# pycopter_board_v1.net
KiCad netlist of a schematic drawn in EAGLE
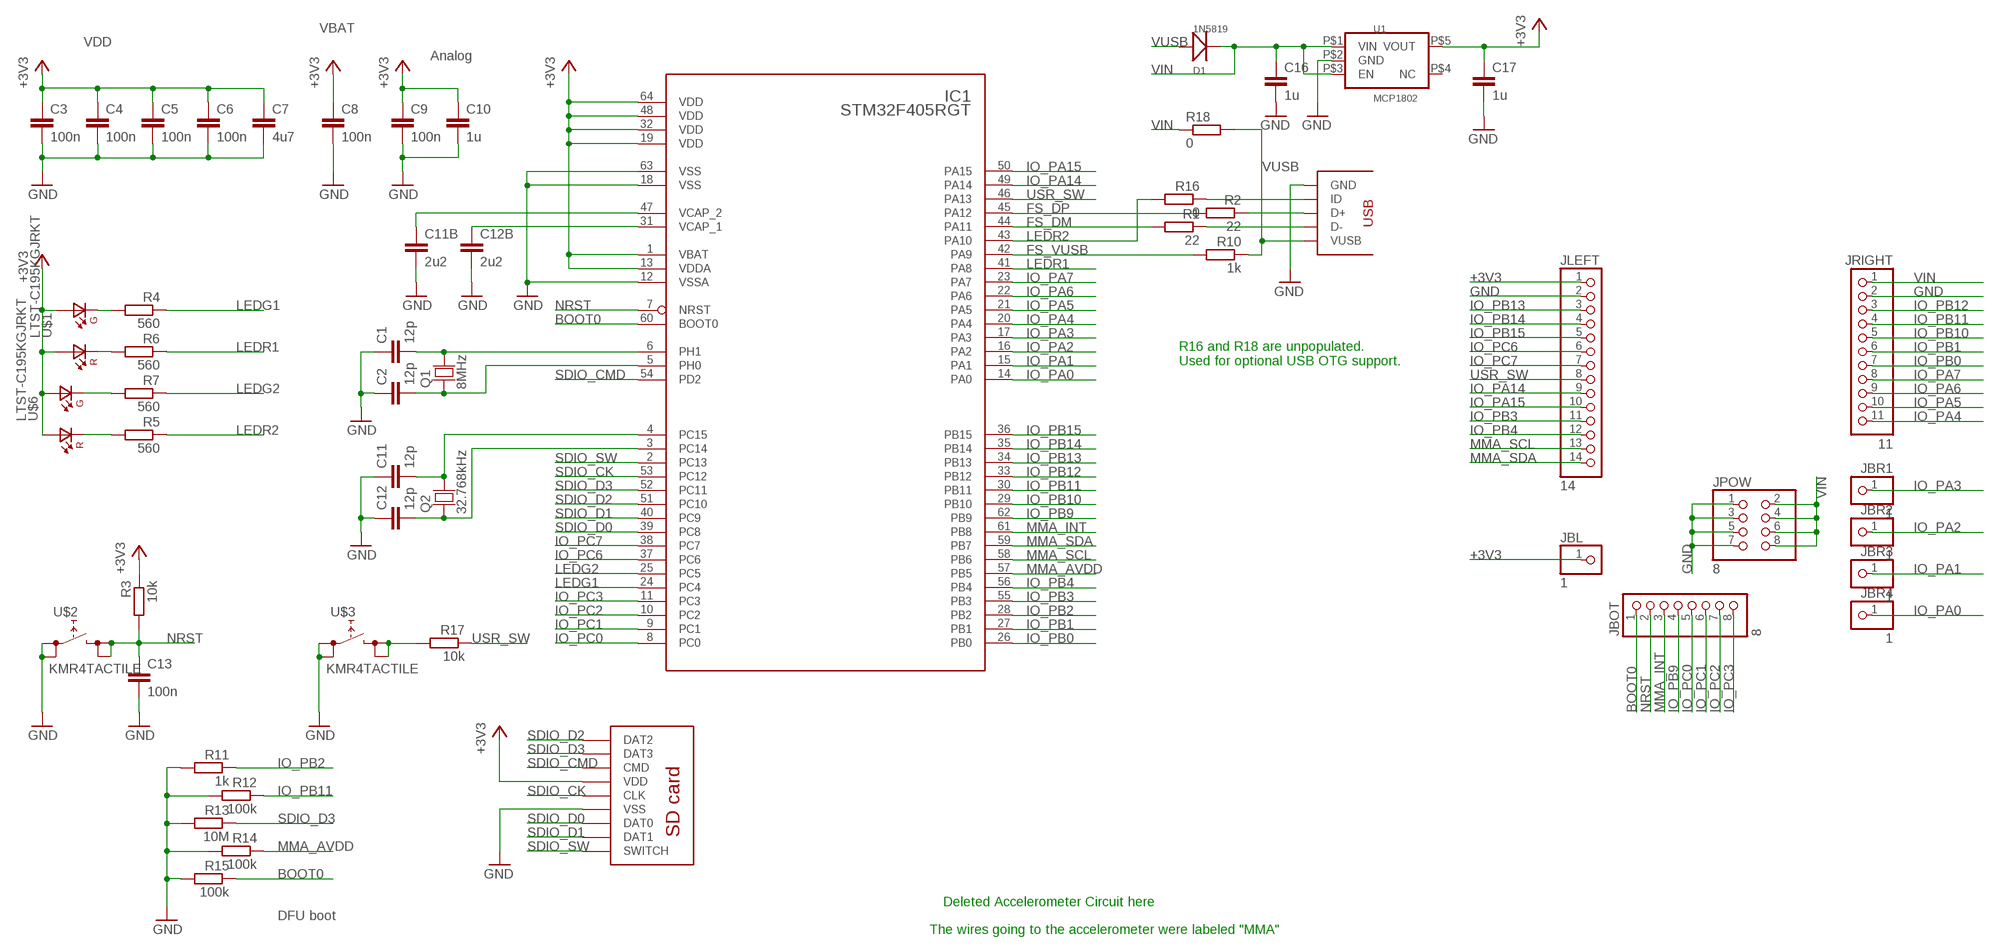
[diagram p0: schematic, sheet 1]

(export (version "E")
  (design (tool "Eeschema 10.0.6"))
  (components
    (comp (ref "C1")
      (value "12p")
      (footprint "eagle-import:C0603")
      (libsource (lib "eagle-import") (part "C-EUC0603"))
    )
    (comp (ref "C2")
      (value "12p")
      (footprint "eagle-import:C0603")
      (libsource (lib "eagle-import") (part "C-EUC0603"))
    )
    (comp (ref "C3")
      (value "100n")
      (footprint "eagle-import:C0603")
      (libsource (lib "eagle-import") (part "C-EUC0603"))
    )
    (comp (ref "C4")
      (value "100n")
      (footprint "eagle-import:C0603")
      (libsource (lib "eagle-import") (part "C-EUC0603"))
    )
    (comp (ref "C5")
      (value "100n")
      (footprint "eagle-import:C0603")
      (libsource (lib "eagle-import") (part "C-EUC0603"))
    )
    (comp (ref "C6")
      (value "100n")
      (footprint "eagle-import:C0603")
      (libsource (lib "eagle-import") (part "C-EUC0603"))
    )
    (comp (ref "C7")
      (value "4u7")
      (footprint "eagle-import:C0603")
      (libsource (lib "eagle-import") (part "C-EUC0603"))
    )
    (comp (ref "C8")
      (value "100n")
      (footprint "eagle-import:C0603")
      (libsource (lib "eagle-import") (part "C-EUC0603"))
    )
    (comp (ref "C9")
      (value "100n")
      (footprint "eagle-import:C0603")
      (libsource (lib "eagle-import") (part "C-EUC0603"))
    )
    (comp (ref "C10")
      (value "1u")
      (footprint "eagle-import:C0603")
      (libsource (lib "eagle-import") (part "C-EUC0603"))
    )
    (comp (ref "C11")
      (value "12p")
      (footprint "eagle-import:C0603")
      (libsource (lib "eagle-import") (part "C-EUC0603"))
    )
    (comp (ref "C11B")
      (value "2u2")
      (footprint "eagle-import:C0603")
      (libsource (lib "eagle-import") (part "C-EUC0603"))
    )
    (comp (ref "C12")
      (value "12p")
      (footprint "eagle-import:C0603")
      (libsource (lib "eagle-import") (part "C-EUC0603"))
    )
    (comp (ref "C12B")
      (value "2u2")
      (footprint "eagle-import:C0603")
      (libsource (lib "eagle-import") (part "C-EUC0603"))
    )
    (comp (ref "C13")
      (value "100n")
      (footprint "eagle-import:C0603")
      (libsource (lib "eagle-import") (part "C-EUC0603"))
    )
    (comp (ref "C16")
      (value "1u")
      (footprint "eagle-import:C0603")
      (libsource (lib "eagle-import") (part "C-EUC0603"))
    )
    (comp (ref "C17")
      (value "1u")
      (footprint "eagle-import:C0603")
      (libsource (lib "eagle-import") (part "C-EUC0603"))
    )
    (comp (ref "D1")
      (value "1N5819")
      (footprint "eagle-import:SOD-123")
      (libsource (lib "eagle-import") (part "1N5819"))
    )
    (comp (ref "IC1")
      (value "STM32F405RGT")
      (footprint "eagle-import:LQFP64")
      (libsource (lib "eagle-import") (part "STM32F405RTG"))
    )
    (comp (ref "JBL")
      (value "1")
      (footprint "eagle-import:1X01")
      (libsource (lib "eagle-import") (part "PINHD-1X1"))
    )
    (comp (ref "JBOT")
      (value "8")
      (footprint "eagle-import:1X08")
      (libsource (lib "eagle-import") (part "PINHD-1X8"))
    )
    (comp (ref "JBR1")
      (value "1")
      (footprint "eagle-import:1X01")
      (libsource (lib "eagle-import") (part "PINHD-1X1"))
    )
    (comp (ref "JBR2")
      (value "1")
      (footprint "eagle-import:1X01")
      (libsource (lib "eagle-import") (part "PINHD-1X1"))
    )
    (comp (ref "JBR3")
      (value "1")
      (footprint "eagle-import:1X01")
      (libsource (lib "eagle-import") (part "PINHD-1X1"))
    )
    (comp (ref "JBR4")
      (value "1")
      (footprint "eagle-import:1X01")
      (libsource (lib "eagle-import") (part "PINHD-1X1"))
    )
    (comp (ref "JLEFT")
      (value "14")
      (footprint "eagle-import:1X14")
      (libsource (lib "eagle-import") (part "PINHD-1X14"))
    )
    (comp (ref "JPOW")
      (value "8")
      (footprint "eagle-import:2X04")
      (libsource (lib "eagle-import") (part "PINHD-2X4"))
    )
    (comp (ref "JRIGHT")
      (value "11")
      (footprint "eagle-import:1X11")
      (libsource (lib "eagle-import") (part "PINHD-1X11"))
    )
    (comp (ref "Q1")
      (value "8MHz")
      (footprint "eagle-import:TXC-SMD-50X32")
      (libsource (lib "eagle-import") (part "TXC-CRYSTAL50X32"))
    )
    (comp (ref "Q2")
      (value "32.768kHz")
      (footprint "eagle-import:TXC-SMD-32X15")
      (libsource (lib "eagle-import") (part "TXC-CRYSTAL32X15"))
    )
    (comp (ref "R1")
      (value "22")
      (footprint "eagle-import:R0603")
      (libsource (lib "eagle-import") (part "R-EU_R0603"))
    )
    (comp (ref "R2")
      (value "22")
      (footprint "eagle-import:R0603")
      (libsource (lib "eagle-import") (part "R-EU_R0603"))
    )
    (comp (ref "R3")
      (value "10k")
      (footprint "eagle-import:R0603")
      (libsource (lib "eagle-import") (part "R-EU_R0603"))
    )
    (comp (ref "R4")
      (value "560")
      (footprint "eagle-import:R0603")
      (libsource (lib "eagle-import") (part "R-EU_R0603"))
    )
    (comp (ref "R5")
      (value "560")
      (footprint "eagle-import:R0603")
      (libsource (lib "eagle-import") (part "R-EU_R0603"))
    )
    (comp (ref "R6")
      (value "560")
      (footprint "eagle-import:R0603")
      (libsource (lib "eagle-import") (part "R-EU_R0603"))
    )
    (comp (ref "R7")
      (value "560")
      (footprint "eagle-import:R0603")
      (libsource (lib "eagle-import") (part "R-EU_R0603"))
    )
    (comp (ref "R10")
      (value "1k")
      (footprint "eagle-import:R0603")
      (libsource (lib "eagle-import") (part "R-EU_R0603"))
    )
    (comp (ref "R11")
      (value "1k")
      (footprint "eagle-import:R0603")
      (libsource (lib "eagle-import") (part "R-EU_R0603"))
    )
    (comp (ref "R12")
      (value "100k")
      (footprint "eagle-import:R0603")
      (libsource (lib "eagle-import") (part "R-EU_R0603"))
    )
    (comp (ref "R13")
      (value "10M")
      (footprint "eagle-import:R0603")
      (libsource (lib "eagle-import") (part "R-EU_R0603"))
    )
    (comp (ref "R14")
      (value "100k")
      (footprint "eagle-import:R0603")
      (libsource (lib "eagle-import") (part "R-EU_R0603"))
    )
    (comp (ref "R15")
      (value "100k")
      (footprint "eagle-import:R0603")
      (libsource (lib "eagle-import") (part "R-EU_R0603"))
    )
    (comp (ref "R16")
      (value "0")
      (footprint "eagle-import:R0603")
      (libsource (lib "eagle-import") (part "R-EU_R0603"))
    )
    (comp (ref "R17")
      (value "10k")
      (footprint "eagle-import:R0603")
      (libsource (lib "eagle-import") (part "R-EU_R0603"))
    )
    (comp (ref "R18")
      (value "0")
      (footprint "eagle-import:R0805")
      (libsource (lib "eagle-import") (part "R-EU_R0805"))
    )
    (comp (ref "U$1")
      (value "LTST-C195KGJRKT")
      (footprint "eagle-import:LTST-BILED-15X16")
      (libsource (lib "eagle-import") (part "LTST-C195KGJRKT"))
    )
    (comp (ref "U$2")
      (value "KMR4TACTILE")
      (footprint "eagle-import:KMR4SWITCH")
      (libsource (lib "eagle-import") (part "KMR4TACTILE"))
    )
    (comp (ref "U$3")
      (value "KMR4TACTILE")
      (footprint "eagle-import:KMR4SWITCH")
      (libsource (lib "eagle-import") (part "KMR4TACTILE"))
    )
    (comp (ref "U$4")
      (value "MOLEX-SD-105027")
      (footprint "eagle-import:MOLEX-SD-105027-PKG")
      (libsource (lib "eagle-import") (part "MOLEX-SD-105027"))
    )
    (comp (ref "U$6")
      (value "LTST-C195KGJRKT")
      (footprint "eagle-import:LTST-BILED-15X16")
      (libsource (lib "eagle-import") (part "LTST-C195KGJRKT"))
    )
    (comp (ref "U$7")
      (value "USB-MICRO-AB")
      (footprint "eagle-import:HRS-USB-ZX62D-AB-5P8-PKG")
      (libsource (lib "eagle-import") (part "USB-MICRO-AB"))
    )
    (comp (ref "U1")
      (value "MCP1802")
      (footprint "eagle-import:SOT-23-5")
      (libsource (lib "eagle-import") (part "MCP1802"))
    )
  )
  (nets
    (net (code "1") (name "+3V3") (class "Default")
      (node (ref "C10") (pin "1") (pinfunction "1_1") (pintype "passive"))
      (node (ref "C17") (pin "1") (pinfunction "1_1") (pintype "passive"))
      (node (ref "C3") (pin "1") (pinfunction "1_1") (pintype "passive"))
      (node (ref "C4") (pin "1") (pinfunction "1_1") (pintype "passive"))
      (node (ref "C5") (pin "1") (pinfunction "1_1") (pintype "passive"))
      (node (ref "C6") (pin "1") (pinfunction "1_1") (pintype "passive"))
      (node (ref "C7") (pin "1") (pinfunction "1_1") (pintype "passive"))
      (node (ref "C8") (pin "1") (pinfunction "1_1") (pintype "passive"))
      (node (ref "C9") (pin "1") (pinfunction "1_1") (pintype "passive"))
      (node (ref "IC1") (pin "1") (pinfunction "VBAT_1") (pintype "power_in"))
      (node (ref "IC1") (pin "13") (pinfunction "VDDA_13") (pintype "power_in"))
      (node (ref "IC1") (pin "19") (pinfunction "VDD_19") (pintype "power_in"))
      (node (ref "IC1") (pin "32") (pinfunction "VDD_32") (pintype "power_in"))
      (node (ref "IC1") (pin "48") (pinfunction "VDD_48") (pintype "power_in"))
      (node (ref "IC1") (pin "64") (pinfunction "VDD_64") (pintype "power_in"))
      (node (ref "JBL") (pin "1") (pinfunction "1_1") (pintype "passive"))
      (node (ref "JLEFT") (pin "1") (pinfunction "1_1") (pintype "passive"))
      (node (ref "R3") (pin "1") (pinfunction "1_1") (pintype "passive"))
      (node (ref "U$1") (pin "P$1") (pinfunction "A1_P$1") (pintype "passive"))
      (node (ref "U$1") (pin "P$2") (pinfunction "A2_P$2") (pintype "passive"))
      (node (ref "U$4") (pin "P$4") (pinfunction "VDD_P$4") (pintype "bidirectional"))
      (node (ref "U$6") (pin "P$1") (pinfunction "A1_P$1") (pintype "passive"))
      (node (ref "U$6") (pin "P$2") (pinfunction "A2_P$2") (pintype "passive"))
      (node (ref "U1") (pin "P$5") (pinfunction "VOUT_P$5") (pintype "power_in"))
    )
    (net (code "2") (name "/BOOT0") (class "Default")
      (node (ref "IC1") (pin "60") (pinfunction "BOOT0_60") (pintype "bidirectional"))
      (node (ref "JBOT") (pin "1") (pinfunction "1_1") (pintype "passive"))
      (node (ref "R15") (pin "1") (pinfunction "1_1") (pintype "passive"))
    )
    (net (code "3") (name "/FS_DM") (class "Default")
      (node (ref "IC1") (pin "44") (pinfunction "PA11_44") (pintype "bidirectional"))
      (node (ref "R1") (pin "2") (pinfunction "2_2") (pintype "passive"))
    )
    (net (code "4") (name "/FS_DP") (class "Default")
      (node (ref "IC1") (pin "45") (pinfunction "PA12_45") (pintype "bidirectional"))
      (node (ref "R2") (pin "2") (pinfunction "2_2") (pintype "passive"))
    )
    (net (code "5") (name "/FS_VUSB") (class "Default")
      (node (ref "IC1") (pin "42") (pinfunction "PA9_42") (pintype "bidirectional"))
      (node (ref "R10") (pin "2") (pinfunction "2_2") (pintype "passive"))
    )
    (net (code "6") (name "/IO_PA0") (class "Default")
      (node (ref "IC1") (pin "14") (pinfunction "PA0_14") (pintype "bidirectional"))
      (node (ref "JBR4") (pin "1") (pinfunction "1_1") (pintype "passive"))
    )
    (net (code "7") (name "/IO_PA1") (class "Default")
      (node (ref "IC1") (pin "15") (pinfunction "PA1_15") (pintype "bidirectional"))
      (node (ref "JBR3") (pin "1") (pinfunction "1_1") (pintype "passive"))
    )
    (net (code "8") (name "/IO_PA2") (class "Default")
      (node (ref "IC1") (pin "16") (pinfunction "PA2_16") (pintype "bidirectional"))
      (node (ref "JBR2") (pin "1") (pinfunction "1_1") (pintype "passive"))
    )
    (net (code "9") (name "/IO_PA3") (class "Default")
      (node (ref "IC1") (pin "17") (pinfunction "PA3_17") (pintype "bidirectional"))
      (node (ref "JBR1") (pin "1") (pinfunction "1_1") (pintype "passive"))
    )
    (net (code "10") (name "/IO_PA4") (class "Default")
      (node (ref "IC1") (pin "20") (pinfunction "PA4_20") (pintype "bidirectional"))
      (node (ref "JRIGHT") (pin "11") (pinfunction "11_11") (pintype "passive"))
    )
    (net (code "11") (name "/IO_PA5") (class "Default")
      (node (ref "IC1") (pin "21") (pinfunction "PA5_21") (pintype "bidirectional"))
      (node (ref "JRIGHT") (pin "10") (pinfunction "10_10") (pintype "passive"))
    )
    (net (code "12") (name "/IO_PA6") (class "Default")
      (node (ref "IC1") (pin "22") (pinfunction "PA6_22") (pintype "bidirectional"))
      (node (ref "JRIGHT") (pin "9") (pinfunction "9_9") (pintype "passive"))
    )
    (net (code "13") (name "/IO_PA7") (class "Default")
      (node (ref "IC1") (pin "23") (pinfunction "PA7_23") (pintype "bidirectional"))
      (node (ref "JRIGHT") (pin "8") (pinfunction "8_8") (pintype "passive"))
    )
    (net (code "14") (name "/IO_PA14") (class "Default")
      (node (ref "IC1") (pin "49") (pinfunction "PA14_49") (pintype "bidirectional"))
      (node (ref "JLEFT") (pin "9") (pinfunction "9_9") (pintype "passive"))
    )
    (net (code "15") (name "/IO_PA15") (class "Default")
      (node (ref "IC1") (pin "50") (pinfunction "PA15_50") (pintype "bidirectional"))
      (node (ref "JLEFT") (pin "10") (pinfunction "10_10") (pintype "passive"))
    )
    (net (code "16") (name "/IO_PB0") (class "Default")
      (node (ref "IC1") (pin "26") (pinfunction "PB0_26") (pintype "bidirectional"))
      (node (ref "JRIGHT") (pin "7") (pinfunction "7_7") (pintype "passive"))
    )
    (net (code "17") (name "/IO_PB1") (class "Default")
      (node (ref "IC1") (pin "27") (pinfunction "PB1_27") (pintype "bidirectional"))
      (node (ref "JRIGHT") (pin "6") (pinfunction "6_6") (pintype "passive"))
    )
    (net (code "18") (name "/IO_PB2") (class "Default")
      (node (ref "IC1") (pin "28") (pinfunction "PB2_28") (pintype "bidirectional"))
      (node (ref "R11") (pin "1") (pinfunction "1_1") (pintype "passive"))
    )
    (net (code "19") (name "/IO_PB3") (class "Default")
      (node (ref "IC1") (pin "55") (pinfunction "PB3_55") (pintype "bidirectional"))
      (node (ref "JLEFT") (pin "11") (pinfunction "11_11") (pintype "passive"))
    )
    (net (code "20") (name "/IO_PB4") (class "Default")
      (node (ref "IC1") (pin "56") (pinfunction "PB4_56") (pintype "bidirectional"))
      (node (ref "JLEFT") (pin "12") (pinfunction "12_12") (pintype "passive"))
    )
    (net (code "21") (name "/IO_PB9") (class "Default")
      (node (ref "IC1") (pin "62") (pinfunction "PB9_62") (pintype "bidirectional"))
      (node (ref "JBOT") (pin "4") (pinfunction "4_4") (pintype "passive"))
    )
    (net (code "22") (name "/IO_PB10") (class "Default")
      (node (ref "IC1") (pin "29") (pinfunction "PB10_29") (pintype "bidirectional"))
      (node (ref "JRIGHT") (pin "5") (pinfunction "5_5") (pintype "passive"))
    )
    (net (code "23") (name "/IO_PB11") (class "Default")
      (node (ref "IC1") (pin "30") (pinfunction "PB11_30") (pintype "bidirectional"))
      (node (ref "JRIGHT") (pin "4") (pinfunction "4_4") (pintype "passive"))
      (node (ref "R12") (pin "1") (pinfunction "1_1") (pintype "passive"))
    )
    (net (code "24") (name "/IO_PB12") (class "Default")
      (node (ref "IC1") (pin "33") (pinfunction "PB12_33") (pintype "bidirectional"))
      (node (ref "JRIGHT") (pin "3") (pinfunction "3_3") (pintype "passive"))
    )
    (net (code "25") (name "/IO_PB13") (class "Default")
      (node (ref "IC1") (pin "34") (pinfunction "PB13_34") (pintype "bidirectional"))
      (node (ref "JLEFT") (pin "3") (pinfunction "3_3") (pintype "passive"))
    )
    (net (code "26") (name "/IO_PB14") (class "Default")
      (node (ref "IC1") (pin "35") (pinfunction "PB14_35") (pintype "bidirectional"))
      (node (ref "JLEFT") (pin "4") (pinfunction "4_4") (pintype "passive"))
    )
    (net (code "27") (name "/IO_PB15") (class "Default")
      (node (ref "IC1") (pin "36") (pinfunction "PB15_36") (pintype "bidirectional"))
      (node (ref "JLEFT") (pin "5") (pinfunction "5_5") (pintype "passive"))
    )
    (net (code "28") (name "/IO_PC0") (class "Default")
      (node (ref "IC1") (pin "8") (pinfunction "PC0_8") (pintype "bidirectional"))
      (node (ref "JBOT") (pin "5") (pinfunction "5_5") (pintype "passive"))
    )
    (net (code "29") (name "/IO_PC1") (class "Default")
      (node (ref "IC1") (pin "9") (pinfunction "PC1_9") (pintype "bidirectional"))
      (node (ref "JBOT") (pin "6") (pinfunction "6_6") (pintype "passive"))
    )
    (net (code "30") (name "/IO_PC2") (class "Default")
      (node (ref "IC1") (pin "10") (pinfunction "PC2_10") (pintype "bidirectional"))
      (node (ref "JBOT") (pin "7") (pinfunction "7_7") (pintype "passive"))
    )
    (net (code "31") (name "/IO_PC3") (class "Default")
      (node (ref "IC1") (pin "11") (pinfunction "PC3_11") (pintype "bidirectional"))
      (node (ref "JBOT") (pin "8") (pinfunction "8_8") (pintype "passive"))
    )
    (net (code "32") (name "/IO_PC6") (class "Default")
      (node (ref "IC1") (pin "37") (pinfunction "PC6_37") (pintype "bidirectional"))
      (node (ref "JLEFT") (pin "6") (pinfunction "6_6") (pintype "passive"))
    )
    (net (code "33") (name "/IO_PC7") (class "Default")
      (node (ref "IC1") (pin "38") (pinfunction "PC7_38") (pintype "bidirectional"))
      (node (ref "JLEFT") (pin "7") (pinfunction "7_7") (pintype "passive"))
    )
    (net (code "34") (name "/LEDG1") (class "Default")
      (node (ref "IC1") (pin "24") (pinfunction "PC4_24") (pintype "bidirectional"))
      (node (ref "R4") (pin "1") (pinfunction "1_1") (pintype "passive"))
    )
    (net (code "35") (name "/LEDG2") (class "Default")
      (node (ref "IC1") (pin "25") (pinfunction "PC5_25") (pintype "bidirectional"))
      (node (ref "R7") (pin "1") (pinfunction "1_1") (pintype "passive"))
    )
    (net (code "36") (name "/LEDR1") (class "Default")
      (node (ref "IC1") (pin "41") (pinfunction "PA8_41") (pintype "bidirectional"))
      (node (ref "R6") (pin "1") (pinfunction "1_1") (pintype "passive"))
    )
    (net (code "37") (name "/LEDR2") (class "Default")
      (node (ref "IC1") (pin "43") (pinfunction "PA10_43") (pintype "bidirectional"))
      (node (ref "R16") (pin "2") (pinfunction "2_2") (pintype "passive"))
      (node (ref "R5") (pin "1") (pinfunction "1_1") (pintype "passive"))
    )
    (net (code "38") (name "/MMA_AVDD") (class "Default")
      (node (ref "IC1") (pin "57") (pinfunction "PB5_57") (pintype "bidirectional"))
      (node (ref "R14") (pin "1") (pinfunction "1_1") (pintype "passive"))
    )
    (net (code "39") (name "/MMA_INT") (class "Default")
      (node (ref "IC1") (pin "61") (pinfunction "PB8_61") (pintype "bidirectional"))
      (node (ref "JBOT") (pin "3") (pinfunction "3_3") (pintype "passive"))
    )
    (net (code "40") (name "/MMA_SCL") (class "Default")
      (node (ref "IC1") (pin "58") (pinfunction "PB6_58") (pintype "bidirectional"))
      (node (ref "JLEFT") (pin "13") (pinfunction "13_13") (pintype "passive"))
    )
    (net (code "41") (name "/MMA_SDA") (class "Default")
      (node (ref "IC1") (pin "59") (pinfunction "PB7_59") (pintype "bidirectional"))
      (node (ref "JLEFT") (pin "14") (pinfunction "14_14") (pintype "passive"))
    )
    (net (code "42") (name "/NRST") (class "Default")
      (node (ref "C13") (pin "1") (pinfunction "1_1") (pintype "passive"))
      (node (ref "IC1") (pin "7") (pinfunction "NRST_7") (pintype "input"))
      (node (ref "JBOT") (pin "2") (pinfunction "2_2") (pintype "passive"))
      (node (ref "R3") (pin "2") (pinfunction "2_2") (pintype "passive"))
      (node (ref "U$2") (pin "P$3") (pinfunction "1_P$3") (pintype "passive"))
      (node (ref "U$2") (pin "P$4") (pinfunction "1_P$4") (pintype "passive"))
    )
    (net (code "43") (name "/SDIO_CK") (class "Default")
      (node (ref "IC1") (pin "53") (pinfunction "PC12_53") (pintype "bidirectional"))
      (node (ref "U$4") (pin "P$5") (pinfunction "CLK_P$5") (pintype "bidirectional"))
    )
    (net (code "44") (name "/SDIO_CMD") (class "Default")
      (node (ref "IC1") (pin "54") (pinfunction "PD2_54") (pintype "bidirectional"))
      (node (ref "U$4") (pin "P$3") (pinfunction "CMD_P$3") (pintype "bidirectional"))
    )
    (net (code "45") (name "/SDIO_D0") (class "Default")
      (node (ref "IC1") (pin "39") (pinfunction "PC8_39") (pintype "bidirectional"))
      (node (ref "U$4") (pin "P$7") (pinfunction "DAT0_P$7") (pintype "bidirectional"))
    )
    (net (code "46") (name "/SDIO_D1") (class "Default")
      (node (ref "IC1") (pin "40") (pinfunction "PC9_40") (pintype "bidirectional"))
      (node (ref "U$4") (pin "P$8") (pinfunction "DAT1_P$8") (pintype "bidirectional"))
    )
    (net (code "47") (name "/SDIO_D2") (class "Default")
      (node (ref "IC1") (pin "51") (pinfunction "PC10_51") (pintype "bidirectional"))
      (node (ref "U$4") (pin "P$1") (pinfunction "DAT2_P$1") (pintype "bidirectional"))
    )
    (net (code "48") (name "/SDIO_D3") (class "Default")
      (node (ref "IC1") (pin "52") (pinfunction "PC11_52") (pintype "bidirectional"))
      (node (ref "R13") (pin "1") (pinfunction "1_1") (pintype "passive"))
      (node (ref "U$4") (pin "P$2") (pinfunction "DAT3_P$2") (pintype "bidirectional"))
    )
    (net (code "49") (name "/SDIO_SW") (class "Default")
      (node (ref "IC1") (pin "2") (pinfunction "PC13_2") (pintype "bidirectional"))
      (node (ref "U$4") (pin "G$1") (pinfunction "SWITCH_G$1") (pintype "bidirectional"))
    )
    (net (code "50") (name "/USR_SW") (class "Default")
      (node (ref "IC1") (pin "46") (pinfunction "PA13_46") (pintype "bidirectional"))
      (node (ref "JLEFT") (pin "8") (pinfunction "8_8") (pintype "passive"))
      (node (ref "R17") (pin "1") (pinfunction "1_1") (pintype "passive"))
    )
    (net (code "51") (name "/VIN") (class "Default")
      (node (ref "C16") (pin "1") (pinfunction "1_1") (pintype "passive"))
      (node (ref "D1") (pin "K") (pinfunction "K_K") (pintype "passive"))
      (node (ref "JPOW") (pin "2") (pinfunction "2_2") (pintype "passive"))
      (node (ref "JPOW") (pin "4") (pinfunction "4_4") (pintype "passive"))
      (node (ref "JPOW") (pin "6") (pinfunction "6_6") (pintype "passive"))
      (node (ref "JPOW") (pin "8") (pinfunction "8_8") (pintype "passive"))
      (node (ref "JRIGHT") (pin "1") (pinfunction "1_1") (pintype "passive"))
      (node (ref "R18") (pin "1") (pinfunction "1_1") (pintype "passive"))
      (node (ref "U1") (pin "P$1") (pinfunction "VIN_P$1") (pintype "power_in"))
      (node (ref "U1") (pin "P$3") (pinfunction "EN_P$3") (pintype "input"))
    )
    (net (code "52") (name "/VUSB") (class "Default")
      (node (ref "D1") (pin "A") (pinfunction "A_A") (pintype "passive"))
      (node (ref "R10") (pin "1") (pinfunction "1_1") (pintype "passive"))
      (node (ref "R18") (pin "2") (pinfunction "2_2") (pintype "passive"))
      (node (ref "U$7") (pin "P$1") (pinfunction "VUSB_P$1") (pintype "power_in"))
    )
    (net (code "53") (name "GND") (class "Default")
      (node (ref "C1") (pin "1") (pinfunction "1_1") (pintype "passive"))
      (node (ref "C10") (pin "2") (pinfunction "2_2") (pintype "passive"))
      (node (ref "C11") (pin "1") (pinfunction "1_1") (pintype "passive"))
      (node (ref "C11B") (pin "2") (pinfunction "2_2") (pintype "passive"))
      (node (ref "C12") (pin "1") (pinfunction "1_1") (pintype "passive"))
      (node (ref "C12B") (pin "2") (pinfunction "2_2") (pintype "passive"))
      (node (ref "C13") (pin "2") (pinfunction "2_2") (pintype "passive"))
      (node (ref "C16") (pin "2") (pinfunction "2_2") (pintype "passive"))
      (node (ref "C17") (pin "2") (pinfunction "2_2") (pintype "passive"))
      (node (ref "C2") (pin "1") (pinfunction "1_1") (pintype "passive"))
      (node (ref "C3") (pin "2") (pinfunction "2_2") (pintype "passive"))
      (node (ref "C4") (pin "2") (pinfunction "2_2") (pintype "passive"))
      (node (ref "C5") (pin "2") (pinfunction "2_2") (pintype "passive"))
      (node (ref "C6") (pin "2") (pinfunction "2_2") (pintype "passive"))
      (node (ref "C7") (pin "2") (pinfunction "2_2") (pintype "passive"))
      (node (ref "C8") (pin "2") (pinfunction "2_2") (pintype "passive"))
      (node (ref "C9") (pin "2") (pinfunction "2_2") (pintype "passive"))
      (node (ref "IC1") (pin "12") (pinfunction "VSSA_12") (pintype "power_in"))
      (node (ref "IC1") (pin "18") (pinfunction "VSS_18") (pintype "power_in"))
      (node (ref "IC1") (pin "63") (pinfunction "VSS_63") (pintype "power_in"))
      (node (ref "JLEFT") (pin "2") (pinfunction "2_2") (pintype "passive"))
      (node (ref "JPOW") (pin "1") (pinfunction "1_1") (pintype "passive"))
      (node (ref "JPOW") (pin "3") (pinfunction "3_3") (pintype "passive"))
      (node (ref "JPOW") (pin "5") (pinfunction "5_5") (pintype "passive"))
      (node (ref "JPOW") (pin "7") (pinfunction "7_7") (pintype "passive"))
      (node (ref "JRIGHT") (pin "2") (pinfunction "2_2") (pintype "passive"))
      (node (ref "R11") (pin "2") (pinfunction "2_2") (pintype "passive"))
      (node (ref "R12") (pin "2") (pinfunction "2_2") (pintype "passive"))
      (node (ref "R13") (pin "2") (pinfunction "2_2") (pintype "passive"))
      (node (ref "R14") (pin "2") (pinfunction "2_2") (pintype "passive"))
      (node (ref "R15") (pin "2") (pinfunction "2_2") (pintype "passive"))
      (node (ref "U$2") (pin "P$1") (pinfunction "0_P$1") (pintype "passive"))
      (node (ref "U$2") (pin "P$2") (pinfunction "0_P$2") (pintype "passive"))
      (node (ref "U$3") (pin "P$1") (pinfunction "0_P$1") (pintype "passive"))
      (node (ref "U$3") (pin "P$2") (pinfunction "0_P$2") (pintype "passive"))
      (node (ref "U$4") (pin "P$6") (pinfunction "VSS_P$6") (pintype "bidirectional"))
      (node (ref "U$7") (pin "P$5") (pinfunction "GND_P$5") (pintype "power_in"))
      (node (ref "U1") (pin "P$2") (pinfunction "GND_P$2") (pintype "power_in"))
    )
    (net (code "54") (name "Net-(IC1-PC14)") (class "Default")
      (node (ref "C12") (pin "2") (pinfunction "2_2") (pintype "passive"))
      (node (ref "IC1") (pin "3") (pinfunction "PC14_3") (pintype "bidirectional"))
      (node (ref "Q2") (pin "P$1") (pinfunction "P$1_P$1") (pintype "passive"))
    )
    (net (code "55") (name "Net-(IC1-PC15)") (class "Default")
      (node (ref "C11") (pin "2") (pinfunction "2_2") (pintype "passive"))
      (node (ref "IC1") (pin "4") (pinfunction "PC15_4") (pintype "bidirectional"))
      (node (ref "Q2") (pin "P$2") (pinfunction "P$2_P$2") (pintype "passive"))
    )
    (net (code "56") (name "Net-(IC1-PH0)") (class "Default")
      (node (ref "C2") (pin "2") (pinfunction "2_2") (pintype "passive"))
      (node (ref "IC1") (pin "5") (pinfunction "PH0_5") (pintype "bidirectional"))
      (node (ref "Q1") (pin "P$1") (pinfunction "P$1_P$1") (pintype "passive"))
    )
    (net (code "57") (name "Net-(IC1-PH1)") (class "Default")
      (node (ref "C1") (pin "2") (pinfunction "2_2") (pintype "passive"))
      (node (ref "IC1") (pin "6") (pinfunction "PH1_6") (pintype "bidirectional"))
      (node (ref "Q1") (pin "P$2") (pinfunction "P$2_P$2") (pintype "passive"))
    )
    (net (code "58") (name "Net-(IC1-VCAP_1)") (class "Default")
      (node (ref "C12B") (pin "1") (pinfunction "1_1") (pintype "passive"))
      (node (ref "IC1") (pin "31") (pinfunction "VCAP_1_31") (pintype "passive"))
    )
    (net (code "59") (name "Net-(IC1-VCAP_2)") (class "Default")
      (node (ref "C11B") (pin "1") (pinfunction "1_1") (pintype "passive"))
      (node (ref "IC1") (pin "47") (pinfunction "VCAP_2_47") (pintype "passive"))
    )
    (net (code "60") (name "Net-(R17-Pad2)") (class "Default")
      (node (ref "R17") (pin "2") (pinfunction "2_2") (pintype "passive"))
      (node (ref "U$3") (pin "P$3") (pinfunction "1_P$3") (pintype "passive"))
      (node (ref "U$3") (pin "P$4") (pinfunction "1_P$4") (pintype "passive"))
    )
    (net (code "61") (name "Net-(U$1-K1)") (class "Default")
      (node (ref "R4") (pin "2") (pinfunction "2_2") (pintype "passive"))
      (node (ref "U$1") (pin "P$3") (pinfunction "K1_P$3") (pintype "passive"))
    )
    (net (code "62") (name "Net-(U$1-K2)") (class "Default")
      (node (ref "R6") (pin "2") (pinfunction "2_2") (pintype "passive"))
      (node (ref "U$1") (pin "P$4") (pinfunction "K2_P$4") (pintype "passive"))
    )
    (net (code "63") (name "Net-(U$6-K1)") (class "Default")
      (node (ref "R7") (pin "2") (pinfunction "2_2") (pintype "passive"))
      (node (ref "U$6") (pin "P$3") (pinfunction "K1_P$3") (pintype "passive"))
    )
    (net (code "64") (name "Net-(U$6-K2)") (class "Default")
      (node (ref "R5") (pin "2") (pinfunction "2_2") (pintype "passive"))
      (node (ref "U$6") (pin "P$4") (pinfunction "K2_P$4") (pintype "passive"))
    )
    (net (code "65") (name "Net-(U$7-D+)") (class "Default")
      (node (ref "R2") (pin "1") (pinfunction "1_1") (pintype "passive"))
      (node (ref "U$7") (pin "P$3") (pinfunction "D+_P$3") (pintype "bidirectional"))
    )
    (net (code "66") (name "Net-(U$7-D-)") (class "Default")
      (node (ref "R1") (pin "1") (pinfunction "1_1") (pintype "passive"))
      (node (ref "U$7") (pin "P$2") (pinfunction "D-_P$2") (pintype "bidirectional"))
    )
    (net (code "67") (name "Net-(U$7-ID)") (class "Default")
      (node (ref "R16") (pin "1") (pinfunction "1_1") (pintype "passive"))
      (node (ref "U$7") (pin "P$4") (pinfunction "ID_P$4") (pintype "bidirectional"))
    )
    (net (code "68") (name "unconnected-(U1-NC-PadP$4)") (class "Default")
      (node (ref "U1") (pin "P$4") (pinfunction "NC_P$4") (pintype "no_connect"))
    )
  )
)
